# PowerDistribution.net
KiCad netlist of a schematic drawn in EAGLE
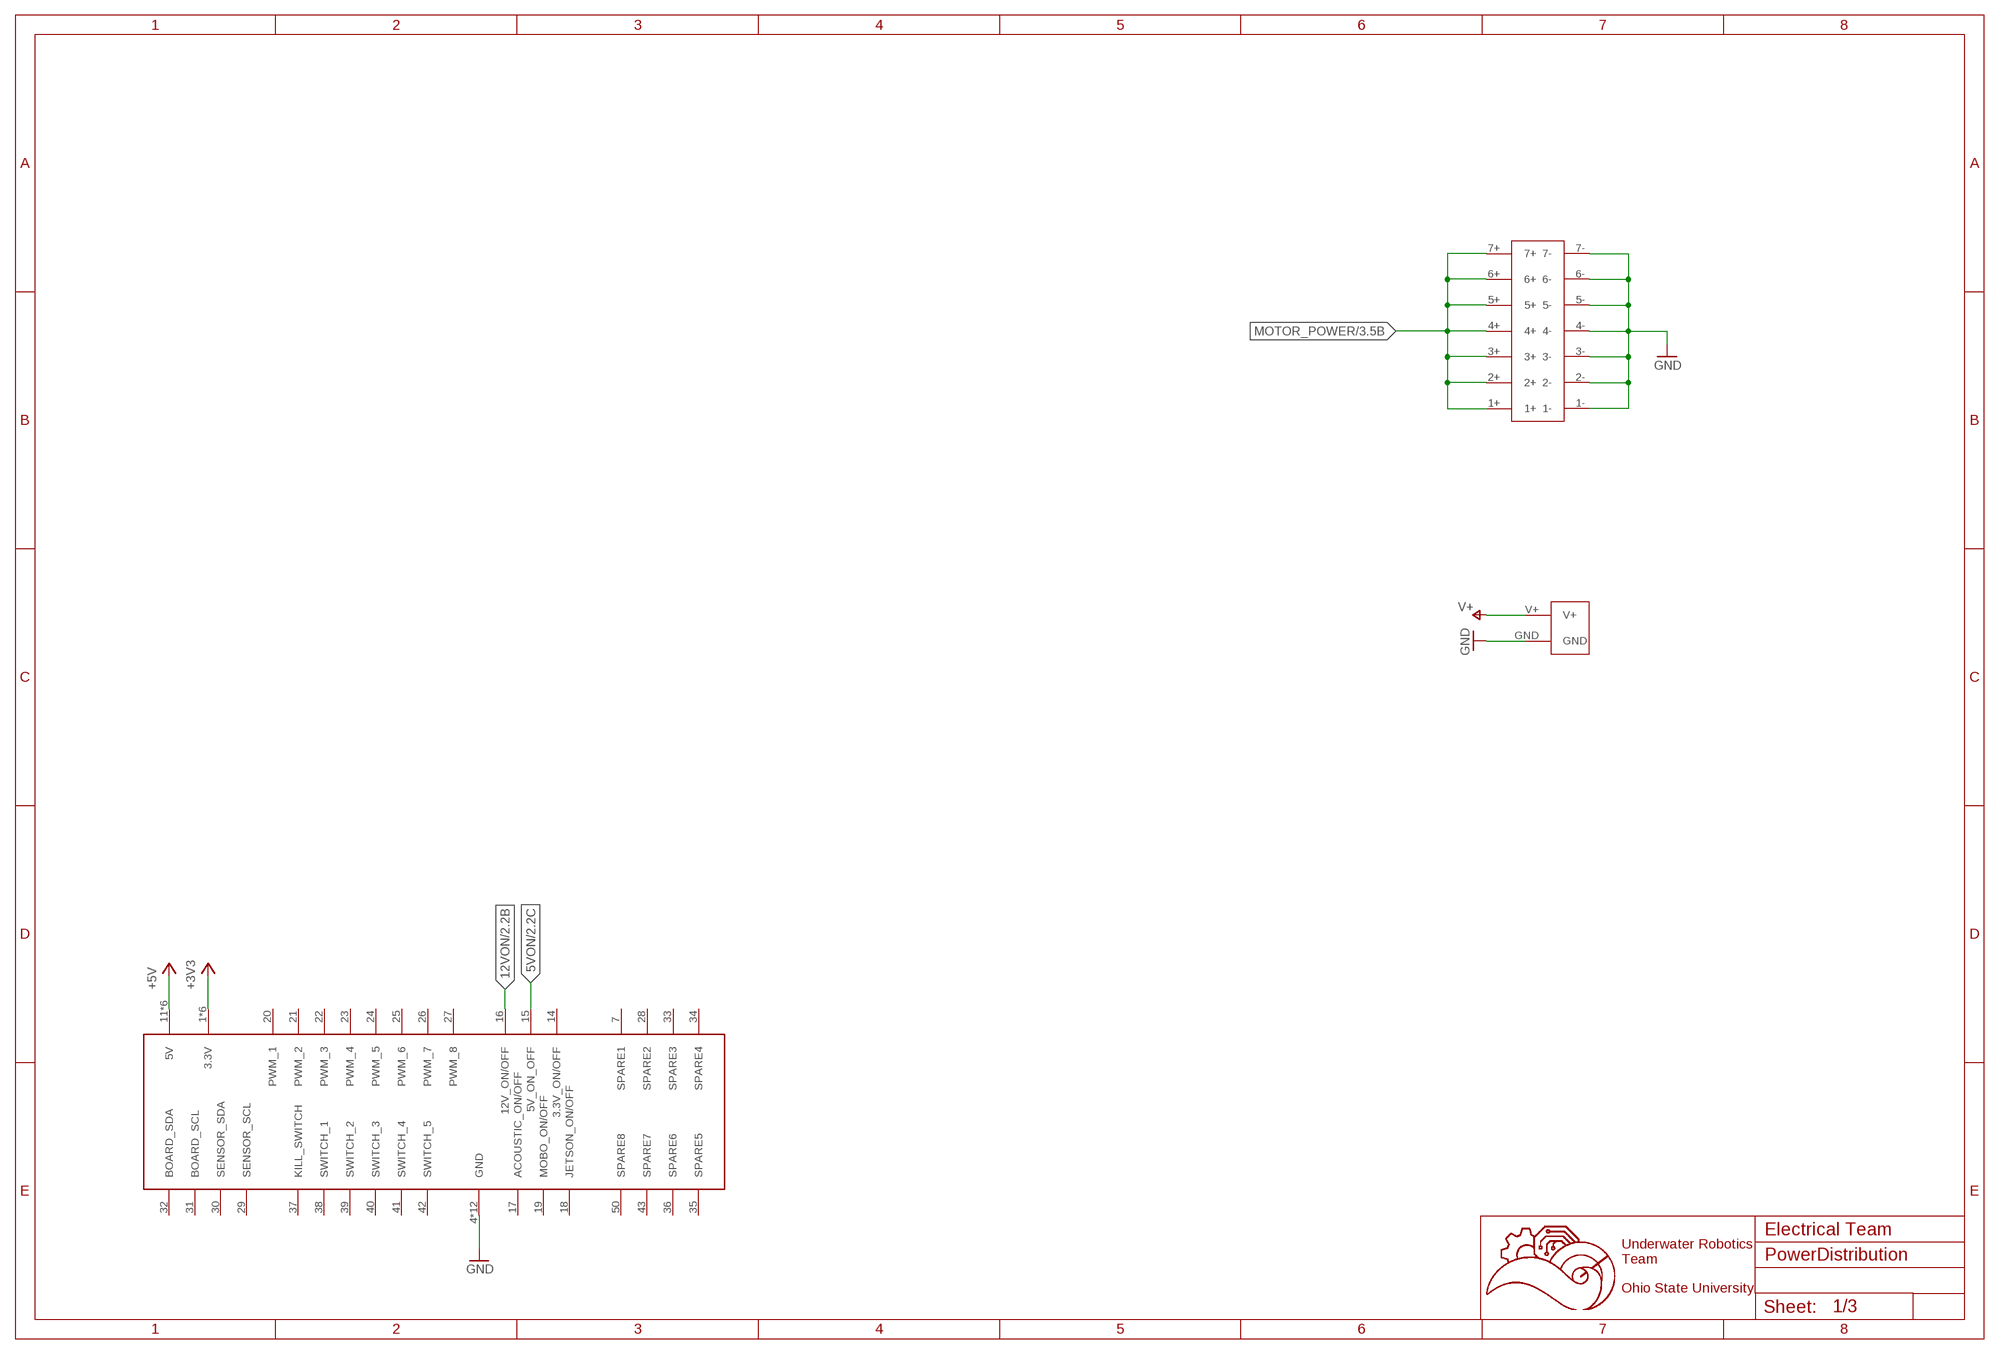
[diagram p0: schematic, sheet 1]
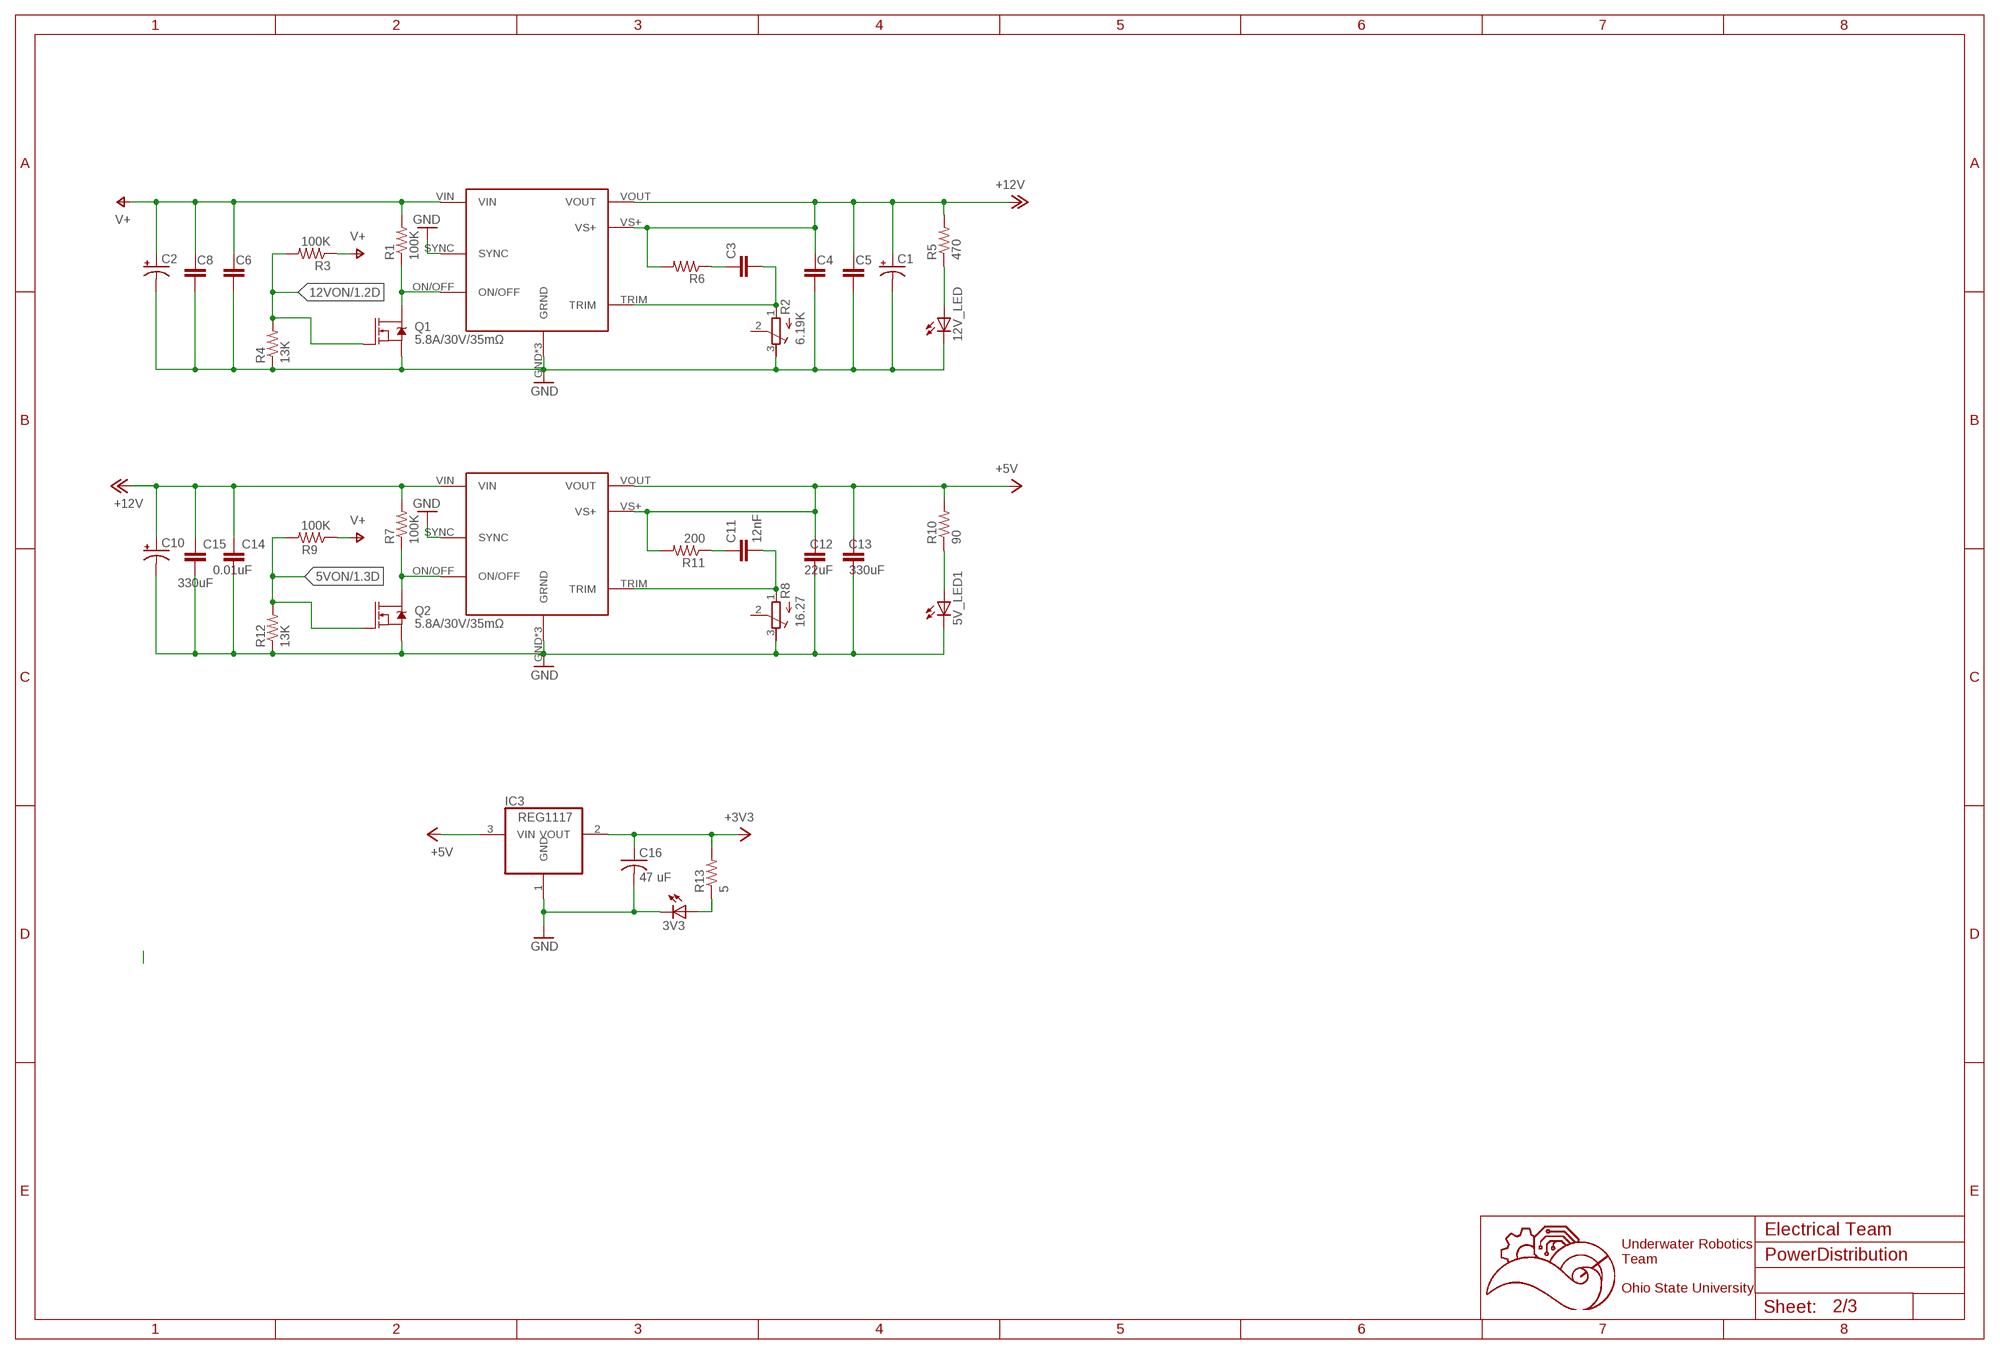
[diagram p1: schematic, sheet 2]
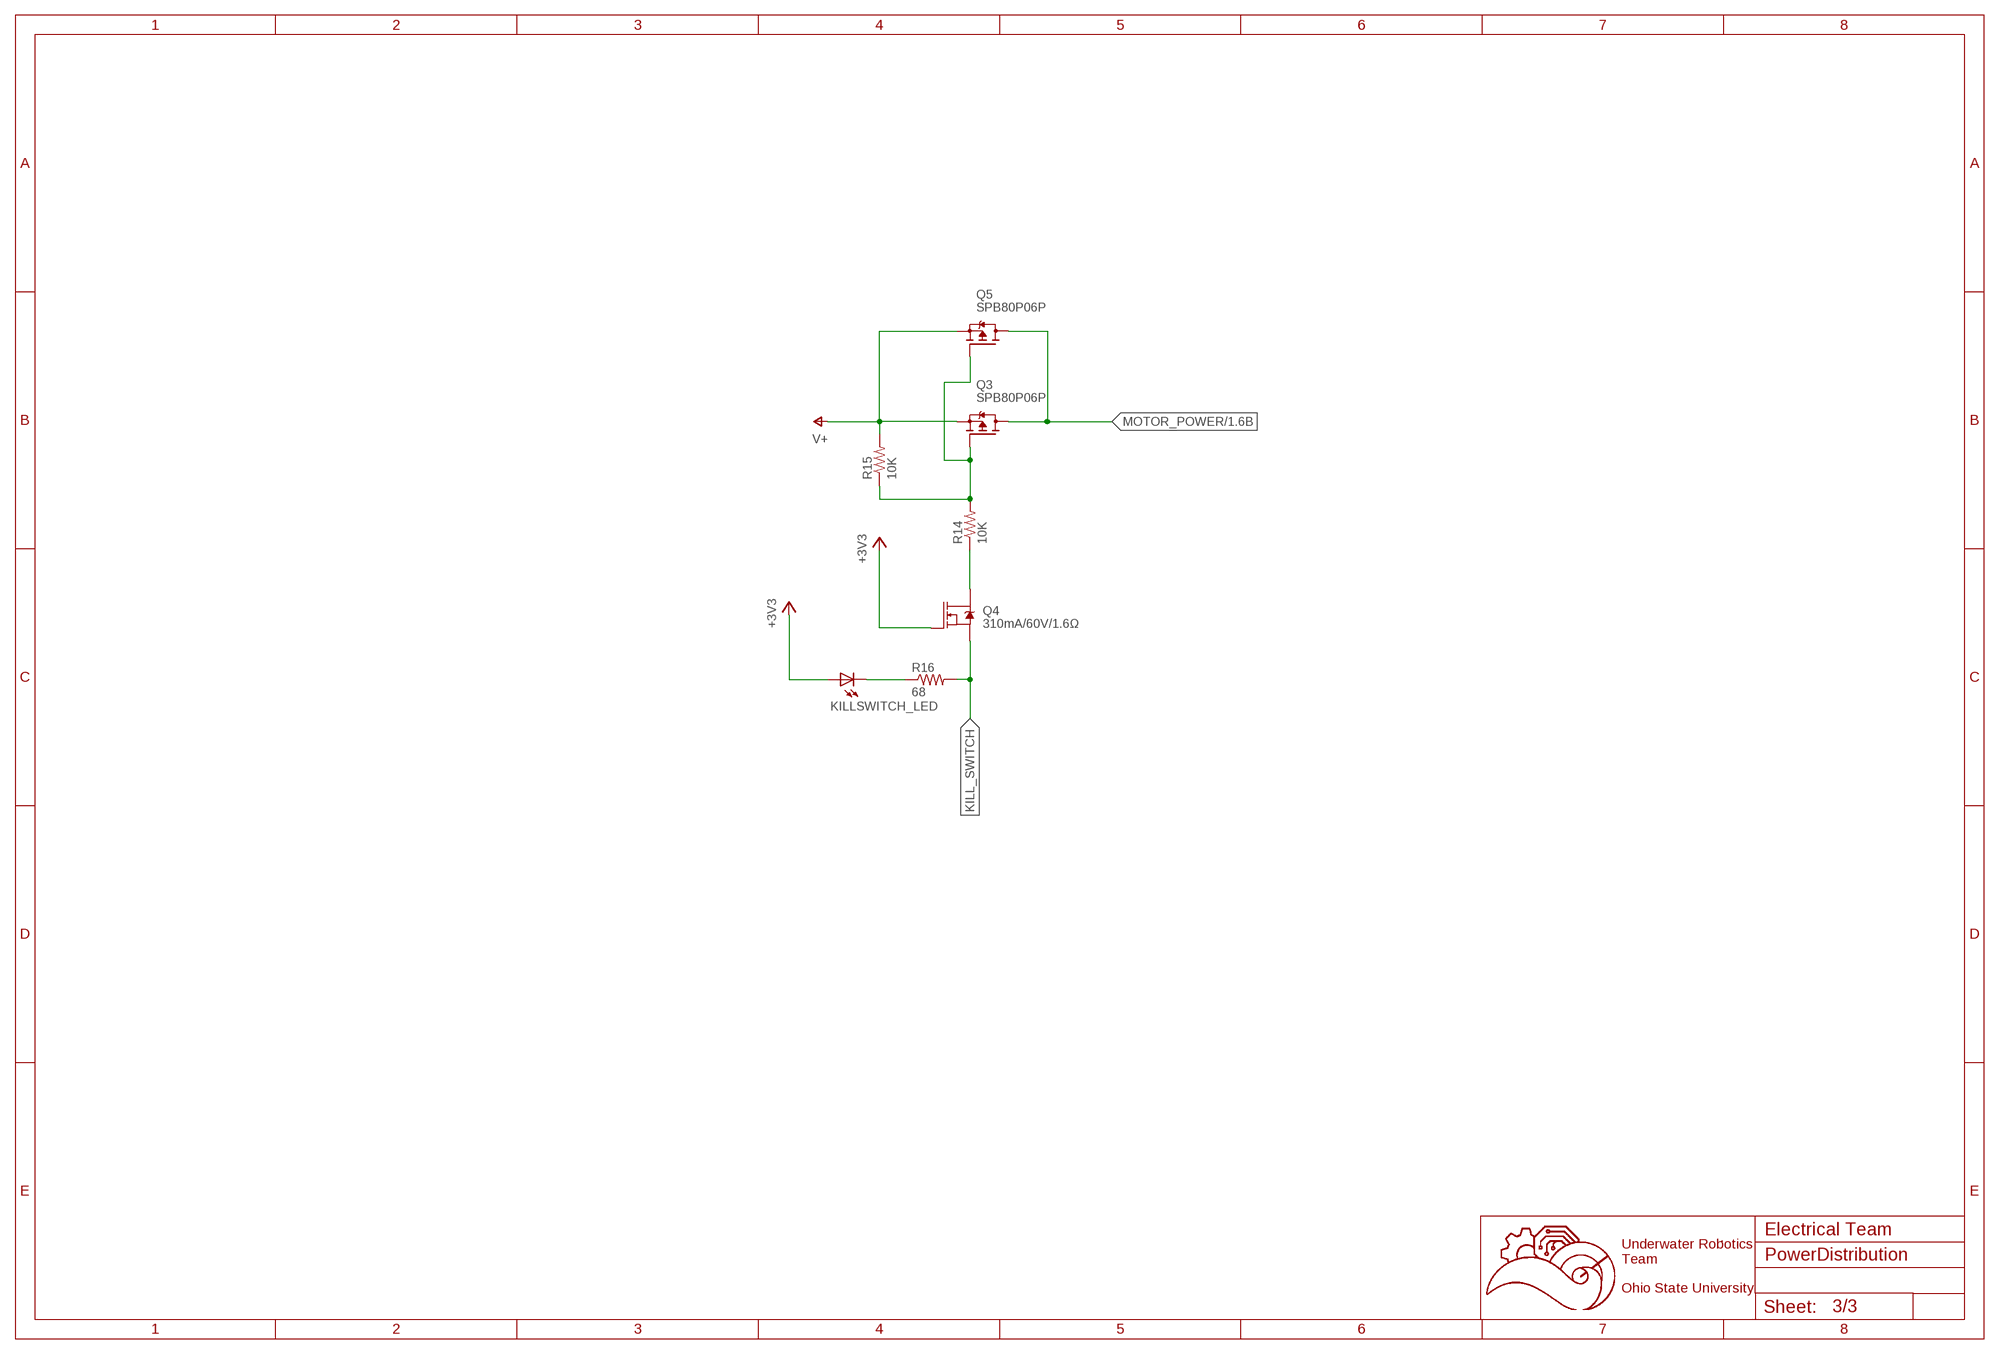
[diagram p2: schematic, sheet 3]

(export (version "E")
  (design (tool "Eeschema 10.0.6"))
  (components
    (comp (ref "KILLSWITCH_LED")
      (value "LEDCHIP-LED0603")
      (footprint "eagle-import:CHIP-LED0603")
      (libsource (lib "eagle-import") (part "LEDCHIP-LED0603"))
    )
    (comp (ref "Q3")
      (value "SPB80P06P")
      (footprint "eagle-import:TO263")
      (libsource (lib "eagle-import") (part "SPB80P06P"))
    )
    (comp (ref "Q4")
      (value "310mA/60V/1.6Ω")
      (footprint "eagle-import:SOT323")
      (libsource (lib "eagle-import") (part "MOSFET-NCH-2N7002PW"))
    )
    (comp (ref "Q5")
      (value "SPB80P06P")
      (footprint "eagle-import:TO263")
      (libsource (lib "eagle-import") (part "SPB80P06P"))
    )
    (comp (ref "R14")
      (value "10K")
      (footprint "eagle-import:R0603")
      (libsource (lib "eagle-import") (part "rcl_334_R-US_R0603"))
    )
    (comp (ref "R15")
      (value "10K")
      (footprint "eagle-import:R0603")
      (libsource (lib "eagle-import") (part "rcl_334_R-US_R0603"))
    )
    (comp (ref "R16")
      (value "68")
      (footprint "eagle-import:R0603")
      (libsource (lib "eagle-import") (part "rcl_334_R-US_R0603"))
    )
    (comp (ref "3V3")
      (value "LEDCHIPLED_0603")
      (footprint "eagle-import:CHIPLED_0603")
      (libsource (lib "eagle-import") (part "LEDCHIPLED_0603"))
    )
    (comp (ref "5V_LED1")
      (value "LEDCHIPLED_0603")
      (footprint "eagle-import:CHIPLED_0603")
      (libsource (lib "eagle-import") (part "LEDCHIPLED_0603"))
    )
    (comp (ref "12V_LED")
      (value "LEDCHIPLED_0603")
      (footprint "eagle-import:CHIPLED_0603")
      (libsource (lib "eagle-import") (part "LEDCHIPLED_0603"))
    )
    (comp (ref "C1")
      (value "CPOL-USE5-10.5")
      (footprint "eagle-import:E5-10,5")
      (libsource (lib "eagle-import") (part "CPOL-USE5-10.5"))
    )
    (comp (ref "C2")
      (value "47uF")
      (footprint "eagle-import:E5-10,5")
      (libsource (lib "eagle-import") (part "CPOL-USE5-10.5"))
    )
    (comp (ref "C3")
      (value "1.5nF")
      (footprint "eagle-import:C0603")
      (libsource (lib "eagle-import") (part "C-EUC0603"))
    )
    (comp (ref "C4")
      (value "22uF")
      (footprint "eagle-import:C0603")
      (libsource (lib "eagle-import") (part "C-EUC0603"))
    )
    (comp (ref "C5")
      (value "470uF")
      (footprint "eagle-import:C0603")
      (libsource (lib "eagle-import") (part "C-EUC0603"))
    )
    (comp (ref "C6")
      (value "0.01uF")
      (footprint "eagle-import:C0603")
      (libsource (lib "eagle-import") (part "C-EUC0603"))
    )
    (comp (ref "C8")
      (value "C-EUC0603")
      (footprint "eagle-import:C0603")
      (libsource (lib "eagle-import") (part "C-EUC0603"))
    )
    (comp (ref "C10")
      (value "47uF")
      (footprint "eagle-import:E5-10,5")
      (libsource (lib "eagle-import") (part "CPOL-USE5-10.5"))
    )
    (comp (ref "C11")
      (value "12nF")
      (footprint "eagle-import:C0603")
      (libsource (lib "eagle-import") (part "C-EUC0603"))
    )
    (comp (ref "C12")
      (value "22uF")
      (footprint "eagle-import:C0603")
      (libsource (lib "eagle-import") (part "C-EUC0603"))
    )
    (comp (ref "C13")
      (value "330uF")
      (footprint "eagle-import:C0603")
      (libsource (lib "eagle-import") (part "C-EUC0603"))
    )
    (comp (ref "C14")
      (value "0.01uF")
      (footprint "eagle-import:C0603")
      (libsource (lib "eagle-import") (part "C-EUC0603"))
    )
    (comp (ref "C15")
      (value "330uF")
      (footprint "eagle-import:C0603")
      (libsource (lib "eagle-import") (part "C-EUC0603"))
    )
    (comp (ref "C16")
      (value "47 uF")
      (footprint "eagle-import:C1206K")
      (libsource (lib "eagle-import") (part "C-USC1206K"))
    )
    (comp (ref "IC3")
      (value "REG1117")
      (footprint "eagle-import:SOT223")
      (libsource (lib "eagle-import") (part "REG1117"))
    )
    (comp (ref "Q1")
      (value "5.8A/30V/35mΩ")
      (footprint "eagle-import:SOT23-3")
      (libsource (lib "eagle-import") (part "MOSFET-NCH-AO3404A"))
    )
    (comp (ref "Q2")
      (value "5.8A/30V/35mΩ")
      (footprint "eagle-import:SOT23-3")
      (libsource (lib "eagle-import") (part "MOSFET-NCH-AO3404A"))
    )
    (comp (ref "R1")
      (value "100K")
      (footprint "eagle-import:R0603")
      (libsource (lib "eagle-import") (part "R-US_R0603"))
    )
    (comp (ref "R2")
      (value "6.19K")
      (footprint "eagle-import:RTRIM3103")
      (libsource (lib "eagle-import") (part "R-TRIMM3103"))
    )
    (comp (ref "R3")
      (value "100K")
      (footprint "eagle-import:R0603")
      (libsource (lib "eagle-import") (part "R-US_R0603"))
    )
    (comp (ref "R4")
      (value "13K")
      (footprint "eagle-import:R0603")
      (libsource (lib "eagle-import") (part "R-US_R0603"))
    )
    (comp (ref "R5")
      (value "470")
      (footprint "eagle-import:R0603")
      (libsource (lib "eagle-import") (part "R-US_R0603"))
    )
    (comp (ref "R6")
      (value "200")
      (footprint "eagle-import:R0603")
      (libsource (lib "eagle-import") (part "R-US_R0603"))
    )
    (comp (ref "R7")
      (value "100K")
      (footprint "eagle-import:R0603")
      (libsource (lib "eagle-import") (part "R-US_R0603"))
    )
    (comp (ref "R8")
      (value "16.27")
      (footprint "eagle-import:RTRIM3103")
      (libsource (lib "eagle-import") (part "R-TRIMM3103"))
    )
    (comp (ref "R9")
      (value "100K")
      (footprint "eagle-import:R0603")
      (libsource (lib "eagle-import") (part "R-US_R0603"))
    )
    (comp (ref "R10")
      (value "90")
      (footprint "eagle-import:R0603")
      (libsource (lib "eagle-import") (part "R-US_R0603"))
    )
    (comp (ref "R11")
      (value "200")
      (footprint "eagle-import:R0603")
      (libsource (lib "eagle-import") (part "R-US_R0603"))
    )
    (comp (ref "R12")
      (value "13K")
      (footprint "eagle-import:R0603")
      (libsource (lib "eagle-import") (part "R-US_R0603"))
    )
    (comp (ref "R13")
      (value "5")
      (footprint "eagle-import:R0603")
      (libsource (lib "eagle-import") (part "rcl_334_R-US_R0603"))
    )
    (comp (ref "U$3")
      (value "DC_DC_CONVERTER")
      (footprint "eagle-import:DC_DC_CONVERTER")
      (libsource (lib "eagle-import") (part "DC_DC_CONVERTER"))
    )
    (comp (ref "U$5")
      (value "DC_DC_CONVERTER")
      (footprint "eagle-import:DC_DC_CONVERTER")
      (libsource (lib "eagle-import") (part "DC_DC_CONVERTER"))
    )
    (comp (ref "U$1")
      (value "5530843-EDGE")
      (footprint "eagle-import:5530843-6-BOARDFINGERS")
      (libsource (lib "eagle-import") (part "5530843-EDGE"))
    )
    (comp (ref "U$2")
      (value "XT90PWH")
      (footprint "eagle-import:XT90PWH")
      (libsource (lib "eagle-import") (part "XT90PWH"))
    )
    (comp (ref "U$4")
      (value "14PIN-VERT")
      (footprint "eagle-import:14PIN_VERT")
      (libsource (lib "eagle-import") (part "14PIN-VERT"))
    )
  )
  (nets
    (net (code "1") (name "+3V3") (class "Default")
      (node (ref "C16") (pin "1") (pinfunction "1_1") (pintype "passive"))
      (node (ref "IC3") (pin "2") (pinfunction "VOUT_2") (pintype "output"))
      (node (ref "KILLSWITCH_LED") (pin "A") (pinfunction "A_A") (pintype "passive"))
      (node (ref "Q4") (pin "1") (pinfunction "G_1") (pintype "bidirectional"))
      (node (ref "R13") (pin "2") (pinfunction "2_2") (pintype "passive"))
      (node (ref "U$1") (pin "1") (pinfunction "3.3V_1") (pintype "bidirectional"))
      (node (ref "U$1") (pin "2") (pinfunction "3.3V_2") (pintype "bidirectional"))
      (node (ref "U$1") (pin "3") (pinfunction "3.3V_3") (pintype "bidirectional"))
      (node (ref "U$1") (pin "54") (pinfunction "3.3V_54") (pintype "bidirectional"))
      (node (ref "U$1") (pin "55") (pinfunction "3.3V_55") (pintype "bidirectional"))
      (node (ref "U$1") (pin "56") (pinfunction "3.3V_56") (pintype "bidirectional"))
    )
    (net (code "2") (name "+5V") (class "Default")
      (node (ref "C12") (pin "2") (pinfunction "2_2") (pintype "passive"))
      (node (ref "C13") (pin "2") (pinfunction "2_2") (pintype "passive"))
      (node (ref "IC3") (pin "3") (pinfunction "VIN_3") (pintype "input"))
      (node (ref "R10") (pin "2") (pinfunction "2_2") (pintype "passive"))
      (node (ref "R11") (pin "2") (pinfunction "2_2") (pintype "passive"))
      (node (ref "U$1") (pin "11") (pinfunction "5V_11") (pintype "bidirectional"))
      (node (ref "U$1") (pin "12") (pinfunction "5V_12") (pintype "bidirectional"))
      (node (ref "U$1") (pin "13") (pinfunction "5V_13") (pintype "bidirectional"))
      (node (ref "U$1") (pin "44") (pinfunction "5V_44") (pintype "bidirectional"))
      (node (ref "U$1") (pin "45") (pinfunction "5V_45") (pintype "bidirectional"))
      (node (ref "U$1") (pin "46") (pinfunction "5V_46") (pintype "bidirectional"))
      (node (ref "U$5") (pin "VOUT") (pinfunction "VOUT_VOUT") (pintype "bidirectional"))
      (node (ref "U$5") (pin "VS+") (pinfunction "VS+_VS+") (pintype "bidirectional"))
    )
    (net (code "3") (name "+12V") (class "Default")
      (node (ref "C1") (pin "+") (pinfunction "+_+") (pintype "passive"))
      (node (ref "C10") (pin "+") (pinfunction "+_+") (pintype "passive"))
      (node (ref "C14") (pin "2") (pinfunction "2_2") (pintype "passive"))
      (node (ref "C15") (pin "2") (pinfunction "2_2") (pintype "passive"))
      (node (ref "C4") (pin "2") (pinfunction "2_2") (pintype "passive"))
      (node (ref "C5") (pin "2") (pinfunction "2_2") (pintype "passive"))
      (node (ref "R5") (pin "2") (pinfunction "2_2") (pintype "passive"))
      (node (ref "R6") (pin "2") (pinfunction "2_2") (pintype "passive"))
      (node (ref "R7") (pin "2") (pinfunction "2_2") (pintype "passive"))
      (node (ref "U$3") (pin "VOUT") (pinfunction "VOUT_VOUT") (pintype "bidirectional"))
      (node (ref "U$3") (pin "VS+") (pinfunction "VS+_VS+") (pintype "bidirectional"))
      (node (ref "U$5") (pin "VIN") (pinfunction "VIN_VIN") (pintype "bidirectional"))
    )
    (net (code "4") (name "5VON") (class "Default")
      (node (ref "Q2") (pin "1") (pinfunction "G_1") (pintype "bidirectional"))
      (node (ref "R12") (pin "2") (pinfunction "2_2") (pintype "passive"))
      (node (ref "R9") (pin "2") (pinfunction "2_2") (pintype "passive"))
      (node (ref "U$1") (pin "15") (pinfunction "5V_ON_OFF_15") (pintype "bidirectional"))
    )
    (net (code "5") (name "12VON") (class "Default")
      (node (ref "Q1") (pin "1") (pinfunction "G_1") (pintype "bidirectional"))
      (node (ref "R3") (pin "2") (pinfunction "2_2") (pintype "passive"))
      (node (ref "R4") (pin "2") (pinfunction "2_2") (pintype "passive"))
      (node (ref "U$1") (pin "16") (pinfunction "12V_ON/OFF_16") (pintype "bidirectional"))
    )
    (net (code "6") (name "GND") (class "Default")
      (node (ref "12V_LED") (pin "C") (pinfunction "C_C") (pintype "passive"))
      (node (ref "3V3") (pin "C") (pinfunction "C_C") (pintype "passive"))
      (node (ref "5V_LED1") (pin "C") (pinfunction "C_C") (pintype "passive"))
      (node (ref "C1") (pin "-") (pinfunction "-_-") (pintype "passive"))
      (node (ref "C10") (pin "-") (pinfunction "-_-") (pintype "passive"))
      (node (ref "C12") (pin "1") (pinfunction "1_1") (pintype "passive"))
      (node (ref "C13") (pin "1") (pinfunction "1_1") (pintype "passive"))
      (node (ref "C14") (pin "1") (pinfunction "1_1") (pintype "passive"))
      (node (ref "C15") (pin "1") (pinfunction "1_1") (pintype "passive"))
      (node (ref "C16") (pin "2") (pinfunction "2_2") (pintype "passive"))
      (node (ref "C2") (pin "-") (pinfunction "-_-") (pintype "passive"))
      (node (ref "C4") (pin "1") (pinfunction "1_1") (pintype "passive"))
      (node (ref "C5") (pin "1") (pinfunction "1_1") (pintype "passive"))
      (node (ref "C6") (pin "1") (pinfunction "1_1") (pintype "passive"))
      (node (ref "C8") (pin "1") (pinfunction "1_1") (pintype "passive"))
      (node (ref "IC3") (pin "1") (pinfunction "GND_1") (pintype "power_in"))
      (node (ref "Q1") (pin "2") (pinfunction "S_2") (pintype "bidirectional"))
      (node (ref "Q2") (pin "2") (pinfunction "S_2") (pintype "bidirectional"))
      (node (ref "R12") (pin "1") (pinfunction "1_1") (pintype "passive"))
      (node (ref "R2") (pin "3") (pinfunction "E_3") (pintype "passive"))
      (node (ref "R4") (pin "1") (pinfunction "1_1") (pintype "passive"))
      (node (ref "R8") (pin "3") (pinfunction "E_3") (pintype "passive"))
      (node (ref "U$1") (pin "10") (pinfunction "GND_10") (pintype "bidirectional"))
      (node (ref "U$1") (pin "4") (pinfunction "GND_4") (pintype "bidirectional"))
      (node (ref "U$1") (pin "47") (pinfunction "GND_47") (pintype "bidirectional"))
      (node (ref "U$1") (pin "48") (pinfunction "GND_48") (pintype "bidirectional"))
      (node (ref "U$1") (pin "49") (pinfunction "GND_49") (pintype "bidirectional"))
      (node (ref "U$1") (pin "5") (pinfunction "GND_5") (pintype "bidirectional"))
      (node (ref "U$1") (pin "51") (pinfunction "GND_51") (pintype "bidirectional"))
      (node (ref "U$1") (pin "52") (pinfunction "GND_52") (pintype "bidirectional"))
      (node (ref "U$1") (pin "53") (pinfunction "GND_53") (pintype "bidirectional"))
      (node (ref "U$1") (pin "6") (pinfunction "GND_6") (pintype "bidirectional"))
      (node (ref "U$1") (pin "8") (pinfunction "GND_8") (pintype "bidirectional"))
      (node (ref "U$1") (pin "9") (pinfunction "GND_9") (pintype "bidirectional"))
      (node (ref "U$2") (pin "GND") (pinfunction "GND_GND") (pintype "bidirectional"))
      (node (ref "U$3") (pin "GND") (pinfunction "GRND_GND") (pintype "bidirectional"))
      (node (ref "U$3") (pin "GND2") (pinfunction "GRND_GND2") (pintype "bidirectional"))
      (node (ref "U$3") (pin "GND3") (pinfunction "GRND_GND3") (pintype "bidirectional"))
      (node (ref "U$3") (pin "SYNC") (pinfunction "SYNC_SYNC") (pintype "bidirectional"))
      (node (ref "U$4") (pin "1-") (pinfunction "1-_1-") (pintype "bidirectional"))
      (node (ref "U$4") (pin "2-") (pinfunction "2-_2-") (pintype "bidirectional"))
      (node (ref "U$4") (pin "3-") (pinfunction "3-_3-") (pintype "bidirectional"))
      (node (ref "U$4") (pin "4-") (pinfunction "4-_4-") (pintype "bidirectional"))
      (node (ref "U$4") (pin "5-") (pinfunction "5-_5-") (pintype "bidirectional"))
      (node (ref "U$4") (pin "6-") (pinfunction "6-_6-") (pintype "bidirectional"))
      (node (ref "U$4") (pin "7-") (pinfunction "7-_7-") (pintype "bidirectional"))
      (node (ref "U$5") (pin "GND") (pinfunction "GRND_GND") (pintype "bidirectional"))
      (node (ref "U$5") (pin "GND2") (pinfunction "GRND_GND2") (pintype "bidirectional"))
      (node (ref "U$5") (pin "GND3") (pinfunction "GRND_GND3") (pintype "bidirectional"))
      (node (ref "U$5") (pin "SYNC") (pinfunction "SYNC_SYNC") (pintype "bidirectional"))
    )
    (net (code "7") (name "KILL_SWITCH") (class "Default")
      (node (ref "Q4") (pin "2") (pinfunction "S_2") (pintype "bidirectional"))
      (node (ref "R16") (pin "2") (pinfunction "2_2") (pintype "passive"))
    )
    (net (code "8") (name "MOTOR_POWER") (class "Default")
      (node (ref "Q3") (pin "3") (pinfunction "D_3") (pintype "passive"))
      (node (ref "Q5") (pin "3") (pinfunction "D_3") (pintype "passive"))
      (node (ref "U$4") (pin "1+") (pinfunction "1+_1+") (pintype "bidirectional"))
      (node (ref "U$4") (pin "2+") (pinfunction "2+_2+") (pintype "bidirectional"))
      (node (ref "U$4") (pin "3+") (pinfunction "3+_3+") (pintype "bidirectional"))
      (node (ref "U$4") (pin "4+") (pinfunction "4+_4+") (pintype "bidirectional"))
      (node (ref "U$4") (pin "5+") (pinfunction "5+_5+") (pintype "bidirectional"))
      (node (ref "U$4") (pin "6+") (pinfunction "6+_6+") (pintype "bidirectional"))
      (node (ref "U$4") (pin "7+") (pinfunction "7+_7+") (pintype "bidirectional"))
    )
    (net (code "9") (name "Net-(3V3-PadA)") (class "Default")
      (node (ref "3V3") (pin "A") (pinfunction "A_A") (pintype "passive"))
      (node (ref "R13") (pin "1") (pinfunction "1_1") (pintype "passive"))
    )
    (net (code "10") (name "Net-(5V_LED1-PadA)") (class "Default")
      (node (ref "5V_LED1") (pin "A") (pinfunction "A_A") (pintype "passive"))
      (node (ref "R10") (pin "1") (pinfunction "1_1") (pintype "passive"))
    )
    (net (code "11") (name "Net-(12V_LED-PadA)") (class "Default")
      (node (ref "12V_LED") (pin "A") (pinfunction "A_A") (pintype "passive"))
      (node (ref "R5") (pin "1") (pinfunction "1_1") (pintype "passive"))
    )
    (net (code "12") (name "Net-(C3-Pad1)") (class "Default")
      (node (ref "C3") (pin "1") (pinfunction "1_1") (pintype "passive"))
      (node (ref "R6") (pin "1") (pinfunction "1_1") (pintype "passive"))
    )
    (net (code "13") (name "Net-(C11-Pad1)") (class "Default")
      (node (ref "C11") (pin "1") (pinfunction "1_1") (pintype "passive"))
      (node (ref "R11") (pin "1") (pinfunction "1_1") (pintype "passive"))
    )
    (net (code "14") (name "Net-(KILLSWITCH_LED-PadC)") (class "Default")
      (node (ref "KILLSWITCH_LED") (pin "C") (pinfunction "C_C") (pintype "passive"))
      (node (ref "R16") (pin "1") (pinfunction "1_1") (pintype "passive"))
    )
    (net (code "15") (name "Net-(Q1-D)") (class "Default")
      (node (ref "Q1") (pin "3") (pinfunction "D_3") (pintype "bidirectional"))
      (node (ref "R1") (pin "1") (pinfunction "1_1") (pintype "passive"))
      (node (ref "U$3") (pin "ON/OFF") (pinfunction "ON/OFF_ON/OFF") (pintype "bidirectional"))
    )
    (net (code "16") (name "Net-(Q2-D)") (class "Default")
      (node (ref "Q2") (pin "3") (pinfunction "D_3") (pintype "bidirectional"))
      (node (ref "R7") (pin "1") (pinfunction "1_1") (pintype "passive"))
      (node (ref "U$5") (pin "ON/OFF") (pinfunction "ON/OFF_ON/OFF") (pintype "bidirectional"))
    )
    (net (code "17") (name "Net-(Q3-G)") (class "Default")
      (node (ref "Q3") (pin "1") (pinfunction "G_1") (pintype "passive"))
      (node (ref "Q5") (pin "1") (pinfunction "G_1") (pintype "passive"))
      (node (ref "R14") (pin "2") (pinfunction "2_2") (pintype "passive"))
      (node (ref "R15") (pin "1") (pinfunction "1_1") (pintype "passive"))
    )
    (net (code "18") (name "Net-(Q4-D)") (class "Default")
      (node (ref "Q4") (pin "3") (pinfunction "D_3") (pintype "bidirectional"))
      (node (ref "R14") (pin "1") (pinfunction "1_1") (pintype "passive"))
    )
    (net (code "19") (name "Net-(R2-A)") (class "Default")
      (node (ref "C3") (pin "2") (pinfunction "2_2") (pintype "passive"))
      (node (ref "R2") (pin "1") (pinfunction "A_1") (pintype "passive"))
      (node (ref "U$3") (pin "TRIM") (pinfunction "TRIM_TRIM") (pintype "bidirectional"))
    )
    (net (code "20") (name "Net-(R8-A)") (class "Default")
      (node (ref "C11") (pin "2") (pinfunction "2_2") (pintype "passive"))
      (node (ref "R8") (pin "1") (pinfunction "A_1") (pintype "passive"))
      (node (ref "U$5") (pin "TRIM") (pinfunction "TRIM_TRIM") (pintype "bidirectional"))
    )
    (net (code "21") (name "V+") (class "Default")
      (node (ref "C2") (pin "+") (pinfunction "+_+") (pintype "passive"))
      (node (ref "C6") (pin "2") (pinfunction "2_2") (pintype "passive"))
      (node (ref "C8") (pin "2") (pinfunction "2_2") (pintype "passive"))
      (node (ref "Q3") (pin "2") (pinfunction "S_2") (pintype "passive"))
      (node (ref "Q5") (pin "2") (pinfunction "S_2") (pintype "passive"))
      (node (ref "R1") (pin "2") (pinfunction "2_2") (pintype "passive"))
      (node (ref "R15") (pin "2") (pinfunction "2_2") (pintype "passive"))
      (node (ref "R3") (pin "1") (pinfunction "1_1") (pintype "passive"))
      (node (ref "R9") (pin "1") (pinfunction "1_1") (pintype "passive"))
      (node (ref "U$2") (pin "V+") (pinfunction "V+_V+") (pintype "bidirectional"))
      (node (ref "U$3") (pin "VIN") (pinfunction "VIN_VIN") (pintype "bidirectional"))
    )
    (net (code "22") (name "unconnected-(R2-S-Pad2)") (class "Default")
      (node (ref "R2") (pin "2") (pinfunction "S_2") (pintype "passive"))
    )
    (net (code "23") (name "unconnected-(R8-S-Pad2)") (class "Default")
      (node (ref "R8") (pin "2") (pinfunction "S_2") (pintype "passive"))
    )
    (net (code "24") (name "unconnected-(U$1-3.3V_ON{slash}OFF-Pad14)") (class "Default")
      (node (ref "U$1") (pin "14") (pinfunction "3.3V_ON/OFF_14") (pintype "bidirectional"))
    )
    (net (code "25") (name "unconnected-(U$1-ACOUSTIC_ON{slash}OFF-Pad17)") (class "Default")
      (node (ref "U$1") (pin "17") (pinfunction "ACOUSTIC_ON/OFF_17") (pintype "bidirectional"))
    )
    (net (code "26") (name "unconnected-(U$1-BOARD_SCL-Pad31)") (class "Default")
      (node (ref "U$1") (pin "31") (pinfunction "BOARD_SCL_31") (pintype "bidirectional"))
    )
    (net (code "27") (name "unconnected-(U$1-BOARD_SDA-Pad32)") (class "Default")
      (node (ref "U$1") (pin "32") (pinfunction "BOARD_SDA_32") (pintype "bidirectional"))
    )
    (net (code "28") (name "unconnected-(U$1-JETSON_ON{slash}OFF-Pad18)") (class "Default")
      (node (ref "U$1") (pin "18") (pinfunction "JETSON_ON/OFF_18") (pintype "bidirectional"))
    )
    (net (code "29") (name "unconnected-(U$1-KILL_SWITCH-Pad37)") (class "Default")
      (node (ref "U$1") (pin "37") (pinfunction "KILL_SWITCH_37") (pintype "output"))
    )
    (net (code "30") (name "unconnected-(U$1-MOBO_ON{slash}OFF-Pad19)") (class "Default")
      (node (ref "U$1") (pin "19") (pinfunction "MOBO_ON/OFF_19") (pintype "bidirectional"))
    )
    (net (code "31") (name "unconnected-(U$1-PWM_1-Pad20)") (class "Default")
      (node (ref "U$1") (pin "20") (pinfunction "PWM_1_20") (pintype "bidirectional"))
    )
    (net (code "32") (name "unconnected-(U$1-PWM_2-Pad21)") (class "Default")
      (node (ref "U$1") (pin "21") (pinfunction "PWM_2_21") (pintype "bidirectional"))
    )
    (net (code "33") (name "unconnected-(U$1-PWM_3-Pad22)") (class "Default")
      (node (ref "U$1") (pin "22") (pinfunction "PWM_3_22") (pintype "bidirectional"))
    )
    (net (code "34") (name "unconnected-(U$1-PWM_4-Pad23)") (class "Default")
      (node (ref "U$1") (pin "23") (pinfunction "PWM_4_23") (pintype "bidirectional"))
    )
    (net (code "35") (name "unconnected-(U$1-PWM_5-Pad24)") (class "Default")
      (node (ref "U$1") (pin "24") (pinfunction "PWM_5_24") (pintype "bidirectional"))
    )
    (net (code "36") (name "unconnected-(U$1-PWM_6-Pad25)") (class "Default")
      (node (ref "U$1") (pin "25") (pinfunction "PWM_6_25") (pintype "bidirectional"))
    )
    (net (code "37") (name "unconnected-(U$1-PWM_7-Pad26)") (class "Default")
      (node (ref "U$1") (pin "26") (pinfunction "PWM_7_26") (pintype "bidirectional"))
    )
    (net (code "38") (name "unconnected-(U$1-PWM_8-Pad27)") (class "Default")
      (node (ref "U$1") (pin "27") (pinfunction "PWM_8_27") (pintype "bidirectional"))
    )
    (net (code "39") (name "unconnected-(U$1-SENSOR_SCL-Pad29)") (class "Default")
      (node (ref "U$1") (pin "29") (pinfunction "SENSOR_SCL_29") (pintype "bidirectional"))
    )
    (net (code "40") (name "unconnected-(U$1-SENSOR_SDA-Pad30)") (class "Default")
      (node (ref "U$1") (pin "30") (pinfunction "SENSOR_SDA_30") (pintype "bidirectional"))
    )
    (net (code "41") (name "unconnected-(U$1-SPARE1-Pad7)") (class "Default")
      (node (ref "U$1") (pin "7") (pinfunction "SPARE1_7") (pintype "bidirectional"))
    )
    (net (code "42") (name "unconnected-(U$1-SPARE2-Pad28)") (class "Default")
      (node (ref "U$1") (pin "28") (pinfunction "SPARE2_28") (pintype "bidirectional"))
    )
    (net (code "43") (name "unconnected-(U$1-SPARE3-Pad33)") (class "Default")
      (node (ref "U$1") (pin "33") (pinfunction "SPARE3_33") (pintype "bidirectional"))
    )
    (net (code "44") (name "unconnected-(U$1-SPARE4-Pad34)") (class "Default")
      (node (ref "U$1") (pin "34") (pinfunction "SPARE4_34") (pintype "bidirectional"))
    )
    (net (code "45") (name "unconnected-(U$1-SPARE5-Pad35)") (class "Default")
      (node (ref "U$1") (pin "35") (pinfunction "SPARE5_35") (pintype "bidirectional"))
    )
    (net (code "46") (name "unconnected-(U$1-SPARE6-Pad36)") (class "Default")
      (node (ref "U$1") (pin "36") (pinfunction "SPARE6_36") (pintype "bidirectional"))
    )
    (net (code "47") (name "unconnected-(U$1-SPARE7-Pad43)") (class "Default")
      (node (ref "U$1") (pin "43") (pinfunction "SPARE7_43") (pintype "bidirectional"))
    )
    (net (code "48") (name "unconnected-(U$1-SPARE8-Pad50)") (class "Default")
      (node (ref "U$1") (pin "50") (pinfunction "SPARE8_50") (pintype "bidirectional"))
    )
    (net (code "49") (name "unconnected-(U$1-SWITCH_1-Pad38)") (class "Default")
      (node (ref "U$1") (pin "38") (pinfunction "SWITCH_1_38") (pintype "output"))
    )
    (net (code "50") (name "unconnected-(U$1-SWITCH_2-Pad39)") (class "Default")
      (node (ref "U$1") (pin "39") (pinfunction "SWITCH_2_39") (pintype "output"))
    )
    (net (code "51") (name "unconnected-(U$1-SWITCH_3-Pad40)") (class "Default")
      (node (ref "U$1") (pin "40") (pinfunction "SWITCH_3_40") (pintype "output"))
    )
    (net (code "52") (name "unconnected-(U$1-SWITCH_4-Pad41)") (class "Default")
      (node (ref "U$1") (pin "41") (pinfunction "SWITCH_4_41") (pintype "output"))
    )
    (net (code "53") (name "unconnected-(U$1-SWITCH_5-Pad42)") (class "Default")
      (node (ref "U$1") (pin "42") (pinfunction "SWITCH_5_42") (pintype "output"))
    )
  )
)
